# PVScontroller_v1_2_with_logo-multiple.net
KiCad netlist of a schematic drawn in EAGLE
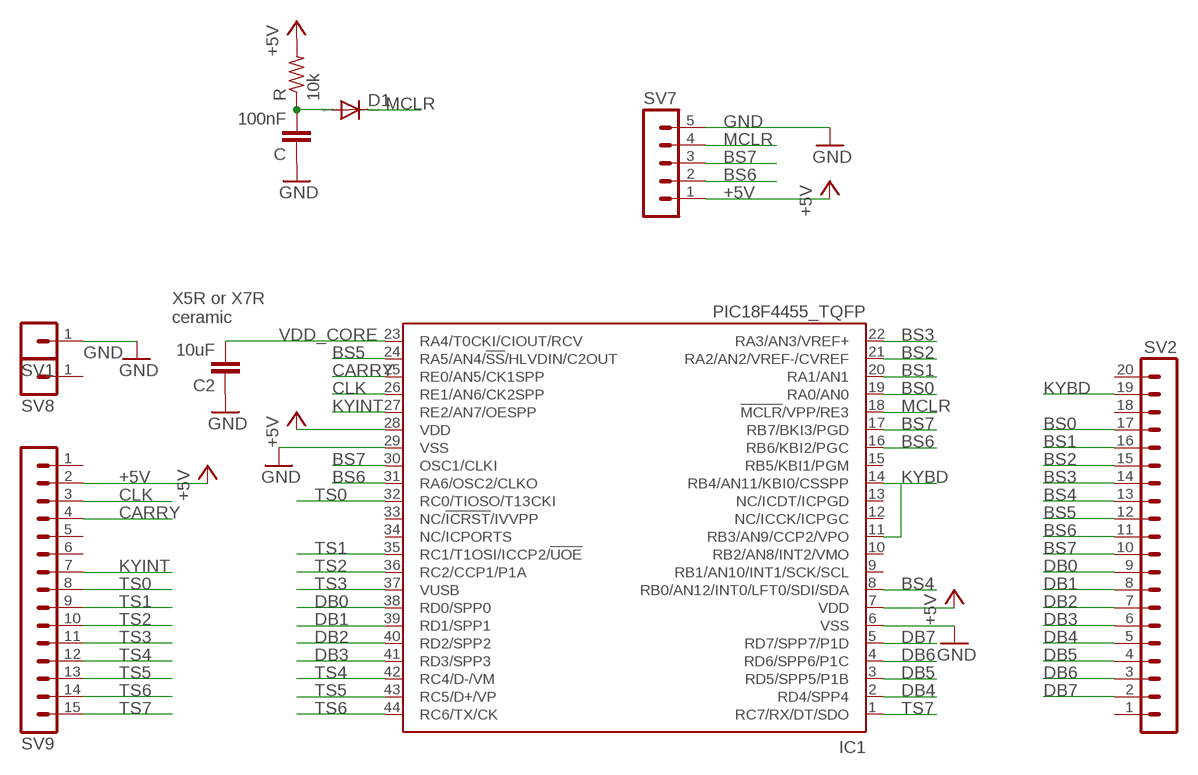
[diagram p0: schematic, sheet 1]

(export (version "E")
  (design (tool "Eeschema 10.0.6"))
  (components
    (comp (ref "C")
      (value "100nF")
      (footprint "eagle-import:C0805")
      (libsource (lib "eagle-import") (part "C-EUC0805"))
    )
    (comp (ref "C2")
      (value "10uF")
      (footprint "eagle-import:C0805")
      (libsource (lib "eagle-import") (part "C-EUC0805"))
    )
    (comp (ref "D1")
      (value "DIODE-SOD80C")
      (footprint "eagle-import:SOD80C")
      (libsource (lib "eagle-import") (part "DIODE-SOD80C"))
    )
    (comp (ref "IC1")
      (value "PIC18F4455_TQFP")
      (footprint "eagle-import:TQFP44")
      (fields (field (name "MF") "MICROCHIP") (field (name "MPN") "PIC18F4455-I/PT"))
      (libsource (lib "eagle-import") (part "PIC18F4_TQFP455"))
    )
    (comp (ref "R")
      (value "10k")
      (footprint "eagle-import:R0805")
      (libsource (lib "eagle-import") (part "R-US_R0805"))
    )
    (comp (ref "SV1")
      (value "MA01-1")
      (footprint "eagle-import:MA01-1")
      (libsource (lib "eagle-import") (part "MA01-1"))
    )
    (comp (ref "SV2")
      (value "MA20-1")
      (footprint "eagle-import:MA20-1")
      (libsource (lib "eagle-import") (part "MA20-1"))
    )
    (comp (ref "SV7")
      (value "MA05-1")
      (footprint "eagle-import:MA05-1")
      (libsource (lib "eagle-import") (part "MA05-1"))
    )
    (comp (ref "SV8")
      (value "MA01-1")
      (footprint "eagle-import:MA01-1")
      (libsource (lib "eagle-import") (part "MA01-1"))
    )
    (comp (ref "SV9")
      (value "MA15-1")
      (footprint "eagle-import:MA15-1")
      (libsource (lib "eagle-import") (part "MA15-1"))
    )
  )
  (nets
    (net (code "1") (name "+5V") (class "Default")
      (node (ref "IC1") (pin "28") (pinfunction "VDD_28") (pintype "power_in"))
      (node (ref "IC1") (pin "7") (pinfunction "VDD_7") (pintype "power_in"))
      (node (ref "R") (pin "2") (pinfunction "2_2") (pintype "passive"))
      (node (ref "SV7") (pin "1") (pinfunction "1_1") (pintype "passive"))
      (node (ref "SV9") (pin "2") (pinfunction "2_2") (pintype "passive"))
    )
    (net (code "2") (name "/BS0") (class "Default")
      (node (ref "IC1") (pin "19") (pinfunction "RA0/AN0_19") (pintype "bidirectional"))
      (node (ref "SV2") (pin "17") (pinfunction "17_17") (pintype "passive"))
    )
    (net (code "3") (name "/BS1") (class "Default")
      (node (ref "IC1") (pin "20") (pinfunction "RA1/AN1_20") (pintype "bidirectional"))
      (node (ref "SV2") (pin "16") (pinfunction "16_16") (pintype "passive"))
    )
    (net (code "4") (name "/BS2") (class "Default")
      (node (ref "IC1") (pin "21") (pinfunction "RA2/AN2/VREF-/CVREF_21") (pintype "bidirectional"))
      (node (ref "SV2") (pin "15") (pinfunction "15_15") (pintype "passive"))
    )
    (net (code "5") (name "/BS3") (class "Default")
      (node (ref "IC1") (pin "22") (pinfunction "RA3/AN3/VREF+_22") (pintype "bidirectional"))
      (node (ref "SV2") (pin "14") (pinfunction "14_14") (pintype "passive"))
    )
    (net (code "6") (name "/BS4") (class "Default")
      (node (ref "IC1") (pin "8") (pinfunction "RB0/AN12/INT0/LFT0/SDI/SDA_8") (pintype "bidirectional"))
      (node (ref "SV2") (pin "13") (pinfunction "13_13") (pintype "passive"))
    )
    (net (code "7") (name "/BS5") (class "Default")
      (node (ref "IC1") (pin "24") (pinfunction "RA5/AN4/~{SS}/HLVDIN/C2OUT_24") (pintype "bidirectional"))
      (node (ref "SV2") (pin "12") (pinfunction "12_12") (pintype "passive"))
    )
    (net (code "8") (name "/BS6") (class "Default")
      (node (ref "IC1") (pin "16") (pinfunction "RB6/KBI2/PGC_16") (pintype "bidirectional"))
      (node (ref "IC1") (pin "31") (pinfunction "RA6/OSC2/CLKO_31") (pintype "output"))
      (node (ref "SV2") (pin "11") (pinfunction "11_11") (pintype "passive"))
      (node (ref "SV7") (pin "2") (pinfunction "2_2") (pintype "passive"))
    )
    (net (code "9") (name "/BS7") (class "Default")
      (node (ref "IC1") (pin "17") (pinfunction "RB7/BKI3/PGD_17") (pintype "bidirectional"))
      (node (ref "IC1") (pin "30") (pinfunction "OSC1/CLKI_30") (pintype "input"))
      (node (ref "SV2") (pin "10") (pinfunction "10_10") (pintype "passive"))
      (node (ref "SV7") (pin "3") (pinfunction "3_3") (pintype "passive"))
    )
    (net (code "10") (name "/CARRY") (class "Default")
      (node (ref "IC1") (pin "25") (pinfunction "RE0/AN5/CK1SPP_25") (pintype "bidirectional"))
      (node (ref "SV9") (pin "4") (pinfunction "4_4") (pintype "passive"))
    )
    (net (code "11") (name "/CLK") (class "Default")
      (node (ref "IC1") (pin "26") (pinfunction "RE1/AN6/CK2SPP_26") (pintype "bidirectional"))
      (node (ref "SV9") (pin "3") (pinfunction "3_3") (pintype "passive"))
    )
    (net (code "12") (name "/DB0") (class "Default")
      (node (ref "IC1") (pin "38") (pinfunction "RD0/SPP0_38") (pintype "bidirectional"))
      (node (ref "SV2") (pin "9") (pinfunction "9_9") (pintype "passive"))
    )
    (net (code "13") (name "/DB1") (class "Default")
      (node (ref "IC1") (pin "39") (pinfunction "RD1/SPP1_39") (pintype "bidirectional"))
      (node (ref "SV2") (pin "8") (pinfunction "8_8") (pintype "passive"))
    )
    (net (code "14") (name "/DB2") (class "Default")
      (node (ref "IC1") (pin "40") (pinfunction "RD2/SPP2_40") (pintype "bidirectional"))
      (node (ref "SV2") (pin "7") (pinfunction "7_7") (pintype "passive"))
    )
    (net (code "15") (name "/DB3") (class "Default")
      (node (ref "IC1") (pin "41") (pinfunction "RD3/SPP3_41") (pintype "bidirectional"))
      (node (ref "SV2") (pin "6") (pinfunction "6_6") (pintype "passive"))
    )
    (net (code "16") (name "/DB4") (class "Default")
      (node (ref "IC1") (pin "2") (pinfunction "RD4/SPP4_2") (pintype "bidirectional"))
      (node (ref "SV2") (pin "5") (pinfunction "5_5") (pintype "passive"))
    )
    (net (code "17") (name "/DB5") (class "Default")
      (node (ref "IC1") (pin "3") (pinfunction "RD5/SPP5/P1B_3") (pintype "bidirectional"))
      (node (ref "SV2") (pin "4") (pinfunction "4_4") (pintype "passive"))
    )
    (net (code "18") (name "/DB6") (class "Default")
      (node (ref "IC1") (pin "4") (pinfunction "RD6/SPP6/P1C_4") (pintype "bidirectional"))
      (node (ref "SV2") (pin "3") (pinfunction "3_3") (pintype "passive"))
    )
    (net (code "19") (name "/DB7") (class "Default")
      (node (ref "IC1") (pin "5") (pinfunction "RD7/SPP7/P1D_5") (pintype "bidirectional"))
      (node (ref "SV2") (pin "2") (pinfunction "2_2") (pintype "passive"))
    )
    (net (code "20") (name "/KYBD") (class "Default")
      (node (ref "IC1") (pin "11") (pinfunction "RB3/AN9/CCP2/VPO_11") (pintype "bidirectional"))
      (node (ref "IC1") (pin "14") (pinfunction "RB4/AN11/KBI0/CSSPP_14") (pintype "bidirectional"))
      (node (ref "SV2") (pin "19") (pinfunction "19_19") (pintype "passive"))
    )
    (net (code "21") (name "/KYINT") (class "Default")
      (node (ref "IC1") (pin "27") (pinfunction "RE2/AN7/OESPP_27") (pintype "bidirectional"))
      (node (ref "SV9") (pin "7") (pinfunction "7_7") (pintype "passive"))
    )
    (net (code "22") (name "/MCLR") (class "Default")
      (node (ref "D1") (pin "C") (pinfunction "C_C") (pintype "passive"))
      (node (ref "IC1") (pin "18") (pinfunction "~{MCLR}/VPP/RE3_18") (pintype "input"))
      (node (ref "SV7") (pin "4") (pinfunction "4_4") (pintype "passive"))
    )
    (net (code "23") (name "/TS0") (class "Default")
      (node (ref "IC1") (pin "32") (pinfunction "RC0/TIOSO/T13CKI_32") (pintype "bidirectional"))
      (node (ref "SV9") (pin "8") (pinfunction "8_8") (pintype "passive"))
    )
    (net (code "24") (name "/TS1") (class "Default")
      (node (ref "IC1") (pin "35") (pinfunction "RC1/T1OSI/ICCP2/~{UOE}_35") (pintype "bidirectional"))
      (node (ref "SV9") (pin "9") (pinfunction "9_9") (pintype "passive"))
    )
    (net (code "25") (name "/TS2") (class "Default")
      (node (ref "IC1") (pin "36") (pinfunction "RC2/CCP1/P1A_36") (pintype "bidirectional"))
      (node (ref "SV9") (pin "10") (pinfunction "10_10") (pintype "passive"))
    )
    (net (code "26") (name "/TS3") (class "Default")
      (node (ref "IC1") (pin "37") (pinfunction "VUSB_37") (pintype "bidirectional"))
      (node (ref "SV9") (pin "11") (pinfunction "11_11") (pintype "passive"))
    )
    (net (code "27") (name "/TS4") (class "Default")
      (node (ref "IC1") (pin "42") (pinfunction "RC4/D-/VM_42") (pintype "bidirectional"))
      (node (ref "SV9") (pin "12") (pinfunction "12_12") (pintype "passive"))
    )
    (net (code "28") (name "/TS5") (class "Default")
      (node (ref "IC1") (pin "43") (pinfunction "RC5/D+/VP_43") (pintype "bidirectional"))
      (node (ref "SV9") (pin "13") (pinfunction "13_13") (pintype "passive"))
    )
    (net (code "29") (name "/TS6") (class "Default")
      (node (ref "IC1") (pin "44") (pinfunction "RC6/TX/CK_44") (pintype "bidirectional"))
      (node (ref "SV9") (pin "14") (pinfunction "14_14") (pintype "passive"))
    )
    (net (code "30") (name "/TS7") (class "Default")
      (node (ref "IC1") (pin "1") (pinfunction "RC7/RX/DT/SDO_1") (pintype "bidirectional"))
      (node (ref "SV9") (pin "15") (pinfunction "15_15") (pintype "passive"))
    )
    (net (code "31") (name "/VDD_CORE") (class "Default")
      (node (ref "C2") (pin "2") (pinfunction "2_2") (pintype "passive"))
      (node (ref "IC1") (pin "23") (pinfunction "RA4/T0CKI/CIOUT/RCV_23") (pintype "bidirectional"))
    )
    (net (code "32") (name "GND") (class "Default")
      (node (ref "C") (pin "1") (pinfunction "1_1") (pintype "passive"))
      (node (ref "C2") (pin "1") (pinfunction "1_1") (pintype "passive"))
      (node (ref "IC1") (pin "29") (pinfunction "VSS_29") (pintype "power_in"))
      (node (ref "IC1") (pin "6") (pinfunction "VSS_6") (pintype "power_in"))
      (node (ref "SV1") (pin "1") (pinfunction "1_1") (pintype "passive"))
      (node (ref "SV7") (pin "5") (pinfunction "5_5") (pintype "passive"))
    )
    (net (code "33") (name "Net-(C-Pad2)") (class "Default")
      (node (ref "C") (pin "2") (pinfunction "2_2") (pintype "passive"))
      (node (ref "D1") (pin "A") (pinfunction "A_A") (pintype "passive"))
      (node (ref "R") (pin "1") (pinfunction "1_1") (pintype "passive"))
    )
    (net (code "34") (name "unconnected-(IC1-NC{slash}ICCK{slash}ICPGC-Pad12)") (class "Default")
      (node (ref "IC1") (pin "12") (pinfunction "NC/ICCK/ICPGC_12") (pintype "bidirectional"))
    )
    (net (code "35") (name "unconnected-(IC1-NC{slash}ICDT{slash}ICPGD-Pad13)") (class "Default")
      (node (ref "IC1") (pin "13") (pinfunction "NC/ICDT/ICPGD_13") (pintype "bidirectional"))
    )
    (net (code "36") (name "unconnected-(IC1-NC{slash}ICPORTS-Pad34)") (class "Default")
      (node (ref "IC1") (pin "34") (pinfunction "NC/ICPORTS_34") (pintype "input"))
    )
    (net (code "37") (name "unconnected-(IC1-NC{slash}~{ICRST}{slash}IVVPP-Pad33)") (class "Default")
      (node (ref "IC1") (pin "33") (pinfunction "NC/~{ICRST}/IVVPP_33") (pintype "input"))
    )
    (net (code "38") (name "unconnected-(IC1-RB1{slash}AN10{slash}INT1{slash}SCK{slash}SCL-Pad9)") (class "Default")
      (node (ref "IC1") (pin "9") (pinfunction "RB1/AN10/INT1/SCK/SCL_9") (pintype "bidirectional"))
    )
    (net (code "39") (name "unconnected-(IC1-RB2{slash}AN8{slash}INT2{slash}VMO-Pad10)") (class "Default")
      (node (ref "IC1") (pin "10") (pinfunction "RB2/AN8/INT2/VMO_10") (pintype "bidirectional"))
    )
    (net (code "40") (name "unconnected-(IC1-RB5{slash}KBI1{slash}PGM-Pad15)") (class "Default")
      (node (ref "IC1") (pin "15") (pinfunction "RB5/KBI1/PGM_15") (pintype "bidirectional"))
    )
    (net (code "41") (name "unconnected-(SV2-Pad1)") (class "Default")
      (node (ref "SV2") (pin "1") (pinfunction "1_1") (pintype "passive"))
    )
    (net (code "42") (name "unconnected-(SV2-Pad18)") (class "Default")
      (node (ref "SV2") (pin "18") (pinfunction "18_18") (pintype "passive"))
    )
    (net (code "43") (name "unconnected-(SV2-Pad20)") (class "Default")
      (node (ref "SV2") (pin "20") (pinfunction "20_20") (pintype "passive"))
    )
    (net (code "44") (name "unconnected-(SV8-Pad1)") (class "Default")
      (node (ref "SV8") (pin "1") (pinfunction "1_1") (pintype "passive"))
    )
    (net (code "45") (name "unconnected-(SV9-Pad1)") (class "Default")
      (node (ref "SV9") (pin "1") (pinfunction "1_1") (pintype "passive"))
    )
    (net (code "46") (name "unconnected-(SV9-Pad5)") (class "Default")
      (node (ref "SV9") (pin "5") (pinfunction "5_5") (pintype "passive"))
    )
    (net (code "47") (name "unconnected-(SV9-Pad6)") (class "Default")
      (node (ref "SV9") (pin "6") (pinfunction "6_6") (pintype "passive"))
    )
  )
)
